# Particle2NodeMCU.net
KiCad netlist of a schematic drawn in EAGLE
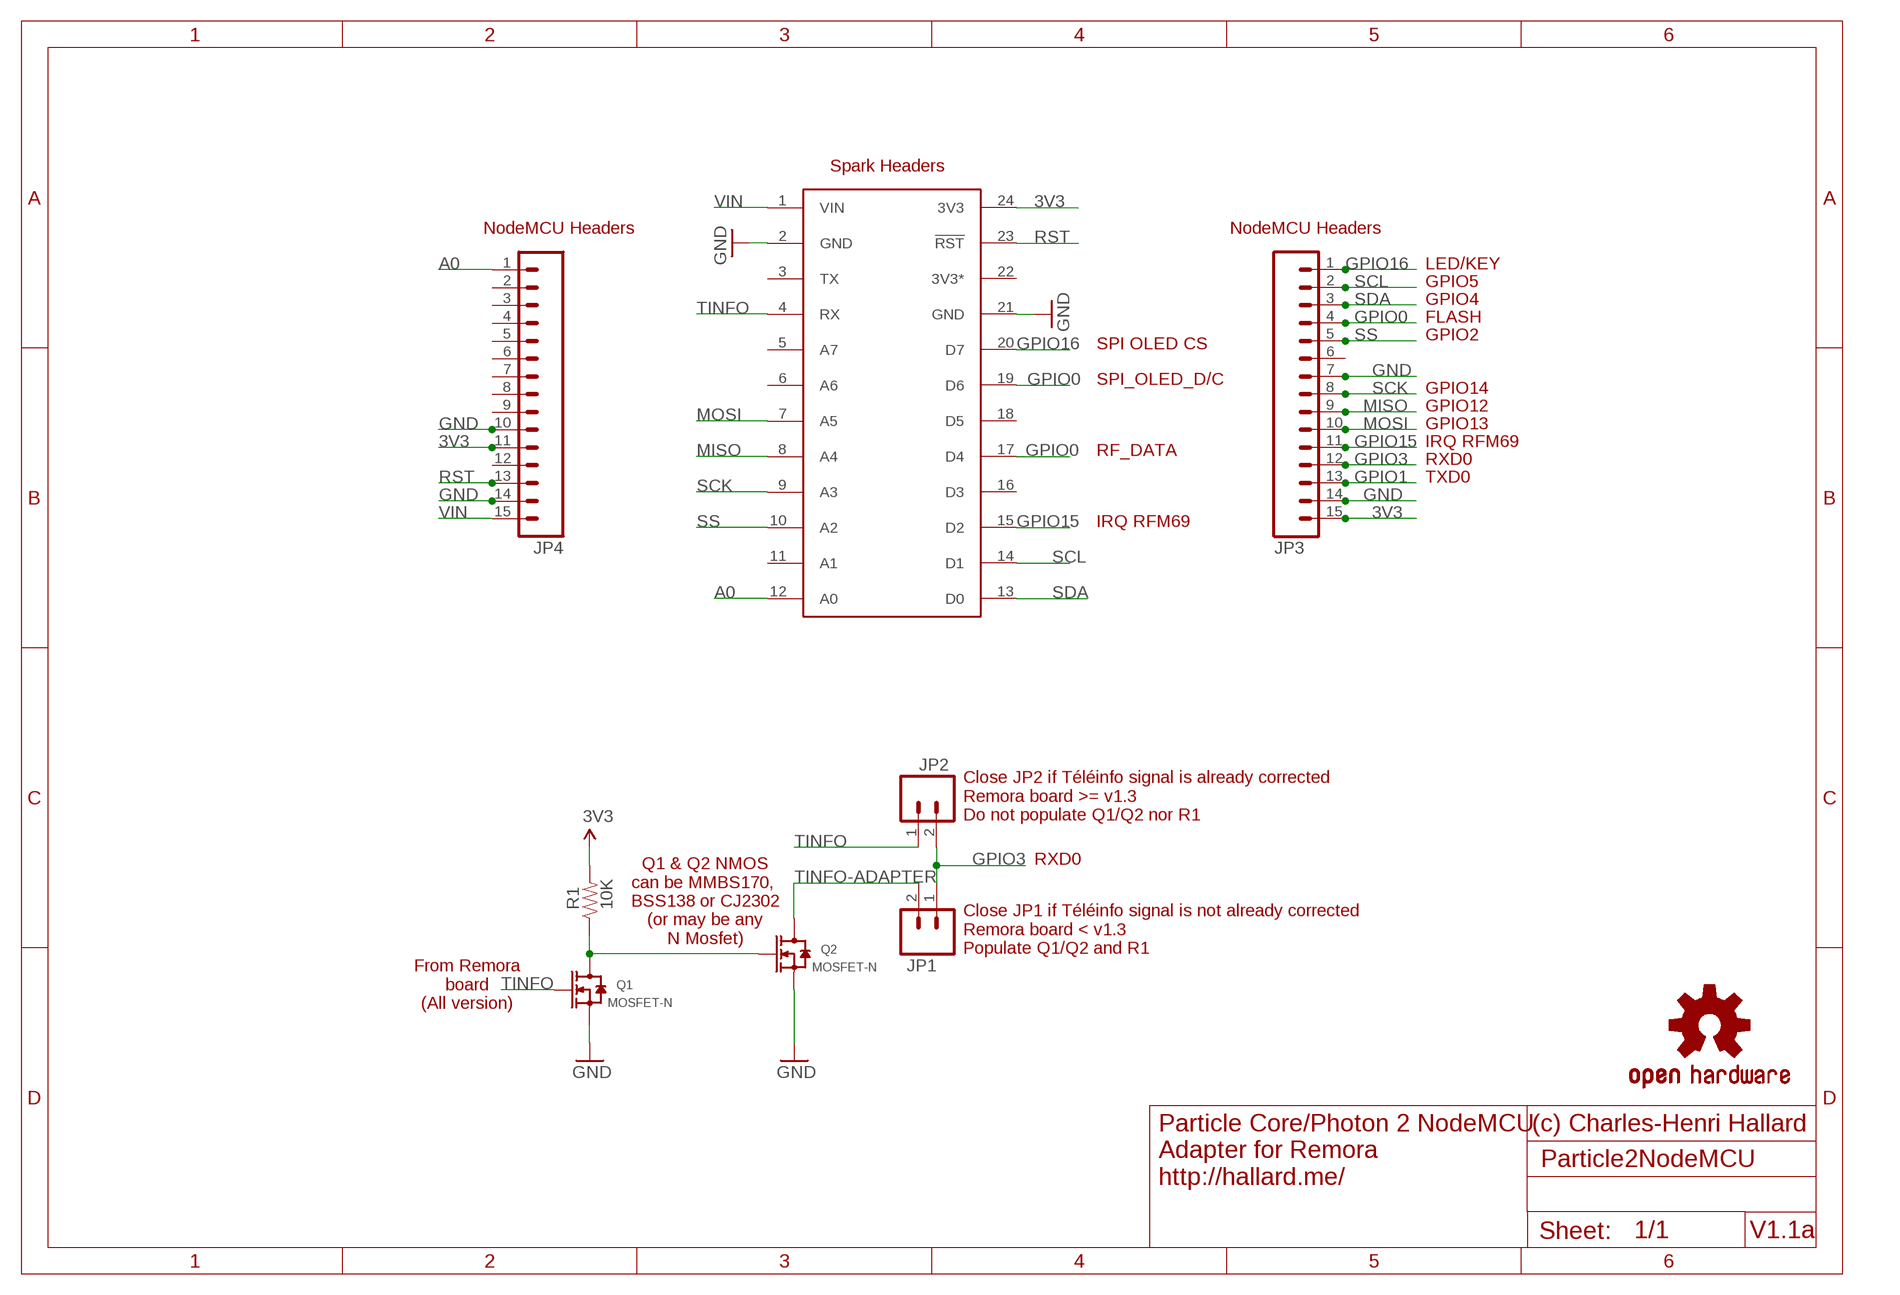
[diagram p0: schematic, sheet 1]

(export (version "E")
  (design (tool "Eeschema 10.0.6"))
  (components
    (comp (ref "JP1")
      (value "M02LOCK")
      (footprint "eagle-import:1X02_LOCK")
      (libsource (lib "eagle-import") (part "M02LOCK"))
    )
    (comp (ref "JP2")
      (value "M02LOCK")
      (footprint "eagle-import:1X02_LOCK")
      (libsource (lib "eagle-import") (part "M02LOCK"))
    )
    (comp (ref "JP3")
      (value "M15")
      (footprint "eagle-import:1X15")
      (libsource (lib "eagle-import") (part "M15"))
    )
    (comp (ref "JP4")
      (value "M15")
      (footprint "eagle-import:1X15")
      (libsource (lib "eagle-import") (part "M15"))
    )
    (comp (ref "LOGO1")
      (value "OSHW-LOGOM")
      (footprint "eagle-import:OSHW-LOGO-M")
      (libsource (lib "eagle-import") (part "OSHW-LOGOM"))
    )
    (comp (ref "LOGO2")
      (value "OSHW-LOGOM")
      (footprint "eagle-import:OSHW-LOGO-M")
      (libsource (lib "eagle-import") (part "OSHW-LOGOM"))
    )
    (comp (ref "Q1")
      (value "MOSFET-N")
      (footprint "eagle-import:SOT23")
      (libsource (lib "eagle-import") (part "MOSFET-N-''"))
    )
    (comp (ref "Q2")
      (value "MOSFET-N")
      (footprint "eagle-import:SOT23")
      (libsource (lib "eagle-import") (part "MOSFET-N-''"))
    )
    (comp (ref "R1")
      (value "10K")
      (footprint "eagle-import:0805-RES")
      (libsource (lib "eagle-import") (part "RESISTOR0805-RES"))
    )
    (comp (ref "U$2")
      (value "SPARK_CORECORE")
      (footprint "eagle-import:SPARK_CORE")
      (libsource (lib "eagle-import") (part "SPARK_CORECORE"))
    )
  )
  (nets
    (net (code "1") (name "/3V3*") (class "Default")
      (node (ref "U$2") (pin "22") (pinfunction "3V3*_22") (pintype "power_in"))
    )
    (net (code "2") (name "/A0") (class "Default")
      (node (ref "JP4") (pin "1") (pinfunction "1_1") (pintype "passive"))
      (node (ref "U$2") (pin "12") (pinfunction "A0_12") (pintype "bidirectional"))
    )
    (net (code "3") (name "/GPIO0") (class "Default")
      (node (ref "JP3") (pin "4") (pinfunction "4_4") (pintype "passive"))
      (node (ref "U$2") (pin "17") (pinfunction "D4_17") (pintype "bidirectional"))
      (node (ref "U$2") (pin "19") (pinfunction "D6_19") (pintype "bidirectional"))
    )
    (net (code "4") (name "/GPIO1") (class "Default")
      (node (ref "JP3") (pin "13") (pinfunction "13_13") (pintype "passive"))
    )
    (net (code "5") (name "/GPIO3") (class "Default")
      (node (ref "JP1") (pin "1") (pinfunction "1_1") (pintype "passive"))
      (node (ref "JP2") (pin "2") (pinfunction "2_2") (pintype "passive"))
      (node (ref "JP3") (pin "12") (pinfunction "12_12") (pintype "passive"))
    )
    (net (code "6") (name "/GPIO15") (class "Default")
      (node (ref "JP3") (pin "11") (pinfunction "11_11") (pintype "passive"))
      (node (ref "U$2") (pin "15") (pinfunction "D2_15") (pintype "bidirectional"))
    )
    (net (code "7") (name "/GPIO16") (class "Default")
      (node (ref "JP3") (pin "1") (pinfunction "1_1") (pintype "passive"))
      (node (ref "U$2") (pin "20") (pinfunction "D7_20") (pintype "bidirectional"))
    )
    (net (code "8") (name "/MISO") (class "Default")
      (node (ref "JP3") (pin "9") (pinfunction "9_9") (pintype "passive"))
      (node (ref "U$2") (pin "8") (pinfunction "A4_8") (pintype "bidirectional"))
    )
    (net (code "9") (name "/MOSI") (class "Default")
      (node (ref "JP3") (pin "10") (pinfunction "10_10") (pintype "passive"))
      (node (ref "U$2") (pin "7") (pinfunction "A5_7") (pintype "bidirectional"))
    )
    (net (code "10") (name "/RST") (class "Default")
      (node (ref "JP4") (pin "13") (pinfunction "13_13") (pintype "passive"))
      (node (ref "U$2") (pin "23") (pinfunction "~{RST}_23") (pintype "bidirectional"))
    )
    (net (code "11") (name "/SCK") (class "Default")
      (node (ref "JP3") (pin "8") (pinfunction "8_8") (pintype "passive"))
      (node (ref "U$2") (pin "9") (pinfunction "A3_9") (pintype "bidirectional"))
    )
    (net (code "12") (name "/SCL") (class "Default")
      (node (ref "JP3") (pin "2") (pinfunction "2_2") (pintype "passive"))
      (node (ref "U$2") (pin "14") (pinfunction "D1_14") (pintype "bidirectional"))
    )
    (net (code "13") (name "/SDA") (class "Default")
      (node (ref "JP3") (pin "3") (pinfunction "3_3") (pintype "passive"))
      (node (ref "U$2") (pin "13") (pinfunction "D0_13") (pintype "bidirectional"))
    )
    (net (code "14") (name "/SS") (class "Default")
      (node (ref "JP3") (pin "5") (pinfunction "5_5") (pintype "passive"))
      (node (ref "U$2") (pin "10") (pinfunction "A2_10") (pintype "bidirectional"))
    )
    (net (code "15") (name "/TINFO") (class "Default")
      (node (ref "JP2") (pin "1") (pinfunction "1_1") (pintype "passive"))
      (node (ref "Q1") (pin "1") (pinfunction "G_1") (pintype "passive"))
      (node (ref "U$2") (pin "4") (pinfunction "RX_4") (pintype "bidirectional"))
    )
    (net (code "16") (name "/TINFO-ADAPTER") (class "Default")
      (node (ref "JP1") (pin "2") (pinfunction "2_2") (pintype "passive"))
      (node (ref "Q2") (pin "3") (pinfunction "D_3") (pintype "passive"))
    )
    (net (code "17") (name "/VIN") (class "Default")
      (node (ref "JP4") (pin "15") (pinfunction "15_15") (pintype "passive"))
      (node (ref "U$2") (pin "1") (pinfunction "VIN_1") (pintype "power_in"))
    )
    (net (code "18") (name "3V3") (class "Default")
      (node (ref "JP3") (pin "15") (pinfunction "15_15") (pintype "passive"))
      (node (ref "JP4") (pin "11") (pinfunction "11_11") (pintype "passive"))
      (node (ref "R1") (pin "2") (pinfunction "2_2") (pintype "passive"))
      (node (ref "U$2") (pin "24") (pinfunction "3V3_24") (pintype "power_in"))
    )
    (net (code "19") (name "GND") (class "Default")
      (node (ref "JP3") (pin "14") (pinfunction "14_14") (pintype "passive"))
      (node (ref "JP3") (pin "7") (pinfunction "7_7") (pintype "passive"))
      (node (ref "JP4") (pin "10") (pinfunction "10_10") (pintype "passive"))
      (node (ref "JP4") (pin "14") (pinfunction "14_14") (pintype "passive"))
      (node (ref "Q1") (pin "2") (pinfunction "S_2") (pintype "passive"))
      (node (ref "Q2") (pin "2") (pinfunction "S_2") (pintype "passive"))
      (node (ref "U$2") (pin "2") (pinfunction "GND_2") (pintype "power_in"))
      (node (ref "U$2") (pin "21") (pinfunction "GND_21") (pintype "power_in"))
    )
    (net (code "20") (name "Net-(Q1-D)") (class "Default")
      (node (ref "Q1") (pin "3") (pinfunction "D_3") (pintype "passive"))
      (node (ref "Q2") (pin "1") (pinfunction "G_1") (pintype "passive"))
      (node (ref "R1") (pin "1") (pinfunction "1_1") (pintype "passive"))
    )
    (net (code "21") (name "unconnected-(JP3-Pad6)") (class "Default")
      (node (ref "JP3") (pin "6") (pinfunction "6_6") (pintype "passive"))
    )
    (net (code "22") (name "unconnected-(JP4-Pad2)") (class "Default")
      (node (ref "JP4") (pin "2") (pinfunction "2_2") (pintype "passive"))
    )
    (net (code "23") (name "unconnected-(JP4-Pad3)") (class "Default")
      (node (ref "JP4") (pin "3") (pinfunction "3_3") (pintype "passive"))
    )
    (net (code "24") (name "unconnected-(JP4-Pad4)") (class "Default")
      (node (ref "JP4") (pin "4") (pinfunction "4_4") (pintype "passive"))
    )
    (net (code "25") (name "unconnected-(JP4-Pad5)") (class "Default")
      (node (ref "JP4") (pin "5") (pinfunction "5_5") (pintype "passive"))
    )
    (net (code "26") (name "unconnected-(JP4-Pad6)") (class "Default")
      (node (ref "JP4") (pin "6") (pinfunction "6_6") (pintype "passive"))
    )
    (net (code "27") (name "unconnected-(JP4-Pad7)") (class "Default")
      (node (ref "JP4") (pin "7") (pinfunction "7_7") (pintype "passive"))
    )
    (net (code "28") (name "unconnected-(JP4-Pad8)") (class "Default")
      (node (ref "JP4") (pin "8") (pinfunction "8_8") (pintype "passive"))
    )
    (net (code "29") (name "unconnected-(JP4-Pad9)") (class "Default")
      (node (ref "JP4") (pin "9") (pinfunction "9_9") (pintype "passive"))
    )
    (net (code "30") (name "unconnected-(JP4-Pad12)") (class "Default")
      (node (ref "JP4") (pin "12") (pinfunction "12_12") (pintype "passive"))
    )
    (net (code "31") (name "unconnected-(U$2-A1-Pad11)") (class "Default")
      (node (ref "U$2") (pin "11") (pinfunction "A1_11") (pintype "bidirectional"))
    )
    (net (code "32") (name "unconnected-(U$2-A6-Pad6)") (class "Default")
      (node (ref "U$2") (pin "6") (pinfunction "A6_6") (pintype "bidirectional"))
    )
    (net (code "33") (name "unconnected-(U$2-A7-Pad5)") (class "Default")
      (node (ref "U$2") (pin "5") (pinfunction "A7_5") (pintype "bidirectional"))
    )
    (net (code "34") (name "unconnected-(U$2-D3-Pad16)") (class "Default")
      (node (ref "U$2") (pin "16") (pinfunction "D3_16") (pintype "bidirectional"))
    )
    (net (code "35") (name "unconnected-(U$2-D5-Pad18)") (class "Default")
      (node (ref "U$2") (pin "18") (pinfunction "D5_18") (pintype "bidirectional"))
    )
    (net (code "36") (name "unconnected-(U$2-TX-Pad3)") (class "Default")
      (node (ref "U$2") (pin "3") (pinfunction "TX_3") (pintype "bidirectional"))
    )
  )
)
